# AD8232.net
KiCad netlist of a schematic drawn in EasyEDA
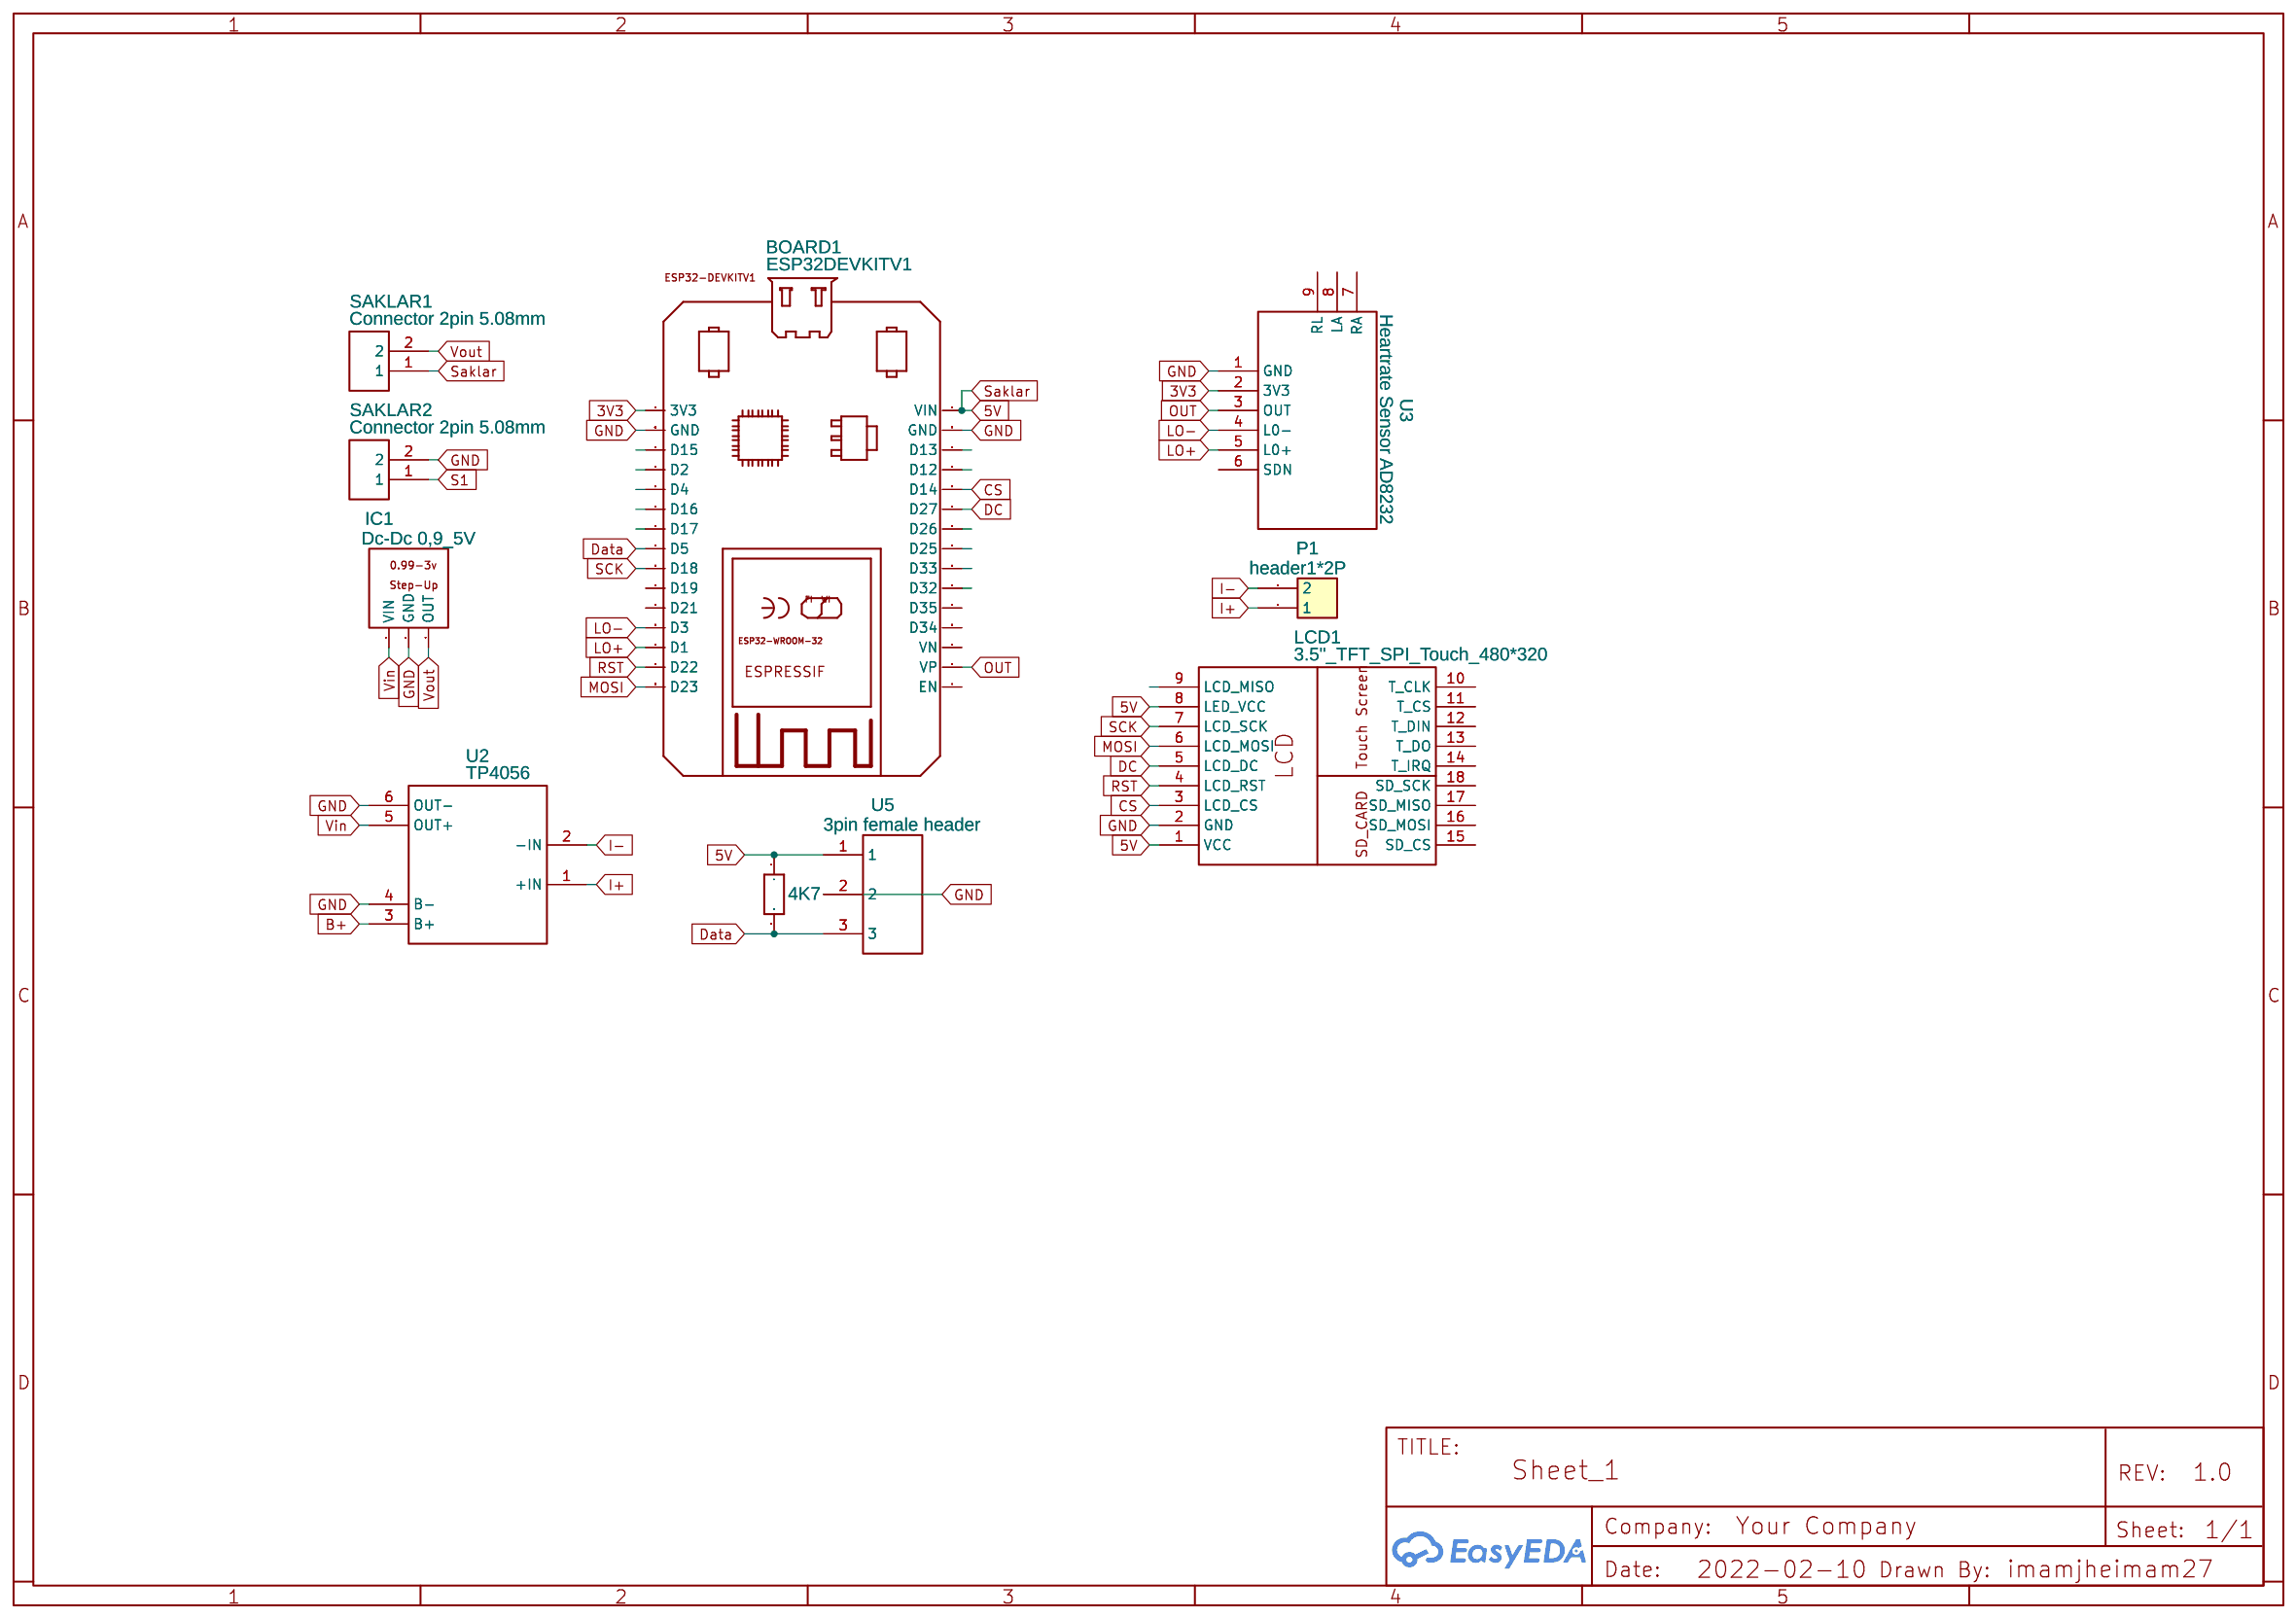
[diagram p0: schematic sheet]

(export (version "E")
  (design (tool "Eeschema 10.0.6"))
  (components
    (comp (ref "4K7") (value ".") (libsource (lib "") (part "NFR25H0002208J")))
    (comp (ref "BOARD1") (value "ESP32DEVKITV1") (libsource (lib "") (part "ESP32DEVKITV1")))
    (comp (ref "IC1") (value "Dc-Dc 0,9_5V") (libsource (lib "") (part "Dc-Dc 0,9_5V")))
    (comp (ref "LCD1")
      (value "3.5\"_TFT_SPI_Touch_480*320")
      (fields (field (name "BOM_Manufacturer Part") "ILI 9488"))
      (libsource (lib "") (part "3.5&quot;_TFT_SPI_Touch_480*320"))
    )
    (comp (ref "P1") (value "header1*2P") (libsource (lib "") (part "header1*2P")))
    (comp (ref "SAKLAR1") (value "Connector 2pin 5.08mm") (libsource (lib "") (part "Connector 2pin 5.08mm")))
    (comp (ref "SAKLAR2") (value "Connector 2pin 5.08mm") (libsource (lib "") (part "Connector 2pin 5.08mm")))
    (comp (ref "U2") (value "TP4056") (libsource (lib "") (part "TP4056")))
    (comp (ref "U3") (value "Heartrate Sensor AD8232") (libsource (lib "") (part "Heartrate Sensor AD8232")))
    (comp (ref "U5") (value "3pin female header") (libsource (lib "") (part "3pin female header")))
  )
  (nets
    (net (code "1") (name "3V3") (class "Default")
      (node (ref "BOARD1") (pin "3V3") (pinfunction "3V3_3V3") (pintype "bidirectional"))
      (node (ref "U3") (pin "2") (pinfunction "3V3_2") (pintype "unspecified"))
    )
    (net (code "2") (name "5V") (class "Default")
      (node (ref "4K7") (pin "1") (pinfunction "1_1") (pintype "bidirectional"))
      (node (ref "BOARD1") (pin "VIN") (pinfunction "VIN_VIN") (pintype "bidirectional"))
      (node (ref "LCD1") (pin "1") (pinfunction "VCC_1") (pintype "unspecified"))
      (node (ref "LCD1") (pin "8") (pinfunction "LED_VCC_8") (pintype "unspecified"))
      (node (ref "SAKLAR1") (pin "1") (pinfunction "1_1") (pintype "unspecified"))
      (node (ref "U5") (pin "1") (pinfunction "1_1") (pintype "unspecified"))
    )
    (net (code "3") (name "B+") (class "Default")
      (node (ref "U2") (pin "3") (pinfunction "B+_3") (pintype "unspecified"))
    )
    (net (code "4") (name "CS") (class "Default")
      (node (ref "BOARD1") (pin "D14") (pinfunction "D14_D14") (pintype "bidirectional"))
      (node (ref "LCD1") (pin "3") (pinfunction "LCD_CS_3") (pintype "unspecified"))
    )
    (net (code "5") (name "DC") (class "Default")
      (node (ref "BOARD1") (pin "D27") (pinfunction "D27_D27") (pintype "bidirectional"))
      (node (ref "LCD1") (pin "5") (pinfunction "LCD_DC_5") (pintype "unspecified"))
    )
    (net (code "6") (name "Data") (class "Default")
      (node (ref "4K7") (pin "2") (pinfunction "2_2") (pintype "bidirectional"))
      (node (ref "BOARD1") (pin "D5") (pinfunction "D5_D5") (pintype "bidirectional"))
      (node (ref "U5") (pin "3") (pinfunction "3_3") (pintype "unspecified"))
    )
    (net (code "7") (name "GND") (class "Default")
      (node (ref "BOARD1") (pin "GND") (pinfunction "GND_GND") (pintype "bidirectional"))
      (node (ref "BOARD1") (pin "GND@1") (pinfunction "GND_GND@1") (pintype "bidirectional"))
      (node (ref "IC1") (pin "2") (pinfunction "GND_2") (pintype "unspecified"))
      (node (ref "LCD1") (pin "2") (pinfunction "GND_2") (pintype "unspecified"))
      (node (ref "SAKLAR2") (pin "2") (pinfunction "2_2") (pintype "unspecified"))
      (node (ref "U2") (pin "4") (pinfunction "B-_4") (pintype "unspecified"))
      (node (ref "U2") (pin "6") (pinfunction "OUT-_6") (pintype "unspecified"))
      (node (ref "U3") (pin "1") (pinfunction "GND_1") (pintype "unspecified"))
      (node (ref "U5") (pin "2") (pinfunction "2_2") (pintype "unspecified"))
    )
    (net (code "8") (name "I+") (class "Default")
      (node (ref "P1") (pin "1") (pinfunction "1_1") (pintype "input"))
      (node (ref "U2") (pin "1") (pinfunction "+IN_1") (pintype "unspecified"))
    )
    (net (code "9") (name "I-") (class "Default")
      (node (ref "P1") (pin "2") (pinfunction "2_2") (pintype "input"))
      (node (ref "U2") (pin "2") (pinfunction "-IN_2") (pintype "unspecified"))
    )
    (net (code "10") (name "LO+") (class "Default")
      (node (ref "BOARD1") (pin "D1") (pinfunction "D1_D1") (pintype "bidirectional"))
      (node (ref "U3") (pin "5") (pinfunction "L0+_5") (pintype "unspecified"))
    )
    (net (code "11") (name "LO-") (class "Default")
      (node (ref "BOARD1") (pin "D3") (pinfunction "D3_D3") (pintype "bidirectional"))
      (node (ref "U3") (pin "4") (pinfunction "L0-_4") (pintype "unspecified"))
    )
    (net (code "12") (name "MOSI") (class "Default")
      (node (ref "BOARD1") (pin "D23") (pinfunction "D23_D23") (pintype "bidirectional"))
      (node (ref "LCD1") (pin "6") (pinfunction "LCD_MOSI_6") (pintype "unspecified"))
    )
    (net (code "13") (name "OUT") (class "Default")
      (node (ref "BOARD1") (pin "VP") (pinfunction "VP_VP") (pintype "bidirectional"))
      (node (ref "U3") (pin "3") (pinfunction "OUT_3") (pintype "unspecified"))
    )
    (net (code "14") (name "RST") (class "Default")
      (node (ref "BOARD1") (pin "D22") (pinfunction "D22_D22") (pintype "bidirectional"))
      (node (ref "LCD1") (pin "4") (pinfunction "LCD_RST_4") (pintype "unspecified"))
    )
    (net (code "15") (name "S1") (class "Default")
      (node (ref "SAKLAR2") (pin "1") (pinfunction "1_1") (pintype "unspecified"))
    )
    (net (code "16") (name "SCK") (class "Default")
      (node (ref "BOARD1") (pin "D18") (pinfunction "D18_D18") (pintype "bidirectional"))
      (node (ref "LCD1") (pin "7") (pinfunction "LCD_SCK_7") (pintype "unspecified"))
    )
    (net (code "17") (name "Vin") (class "Default")
      (node (ref "IC1") (pin "1") (pinfunction "VIN_1") (pintype "unspecified"))
      (node (ref "U2") (pin "5") (pinfunction "OUT+_5") (pintype "unspecified"))
    )
    (net (code "18") (name "Vout") (class "Default")
      (node (ref "IC1") (pin "3") (pinfunction "OUT_3") (pintype "unspecified"))
      (node (ref "SAKLAR1") (pin "2") (pinfunction "2_2") (pintype "unspecified"))
    )
    (net (code "19") (name "unconnected-(BOARD1-PadD2)") (class "Default")
      (node (ref "BOARD1") (pin "D2") (pinfunction "D2_D2") (pintype "bidirectional"))
    )
    (net (code "20") (name "unconnected-(BOARD1-PadD4)") (class "Default")
      (node (ref "BOARD1") (pin "D4") (pinfunction "D4_D4") (pintype "bidirectional"))
    )
    (net (code "21") (name "unconnected-(BOARD1-PadD12)") (class "Default")
      (node (ref "BOARD1") (pin "D12") (pinfunction "D12_D12") (pintype "bidirectional"))
    )
    (net (code "22") (name "unconnected-(BOARD1-PadD13)") (class "Default")
      (node (ref "BOARD1") (pin "D13") (pinfunction "D13_D13") (pintype "bidirectional"))
    )
    (net (code "23") (name "unconnected-(BOARD1-PadD15)") (class "Default")
      (node (ref "BOARD1") (pin "D15") (pinfunction "D15_D15") (pintype "bidirectional"))
    )
    (net (code "24") (name "unconnected-(BOARD1-PadD16)") (class "Default")
      (node (ref "BOARD1") (pin "D16") (pinfunction "D16_D16") (pintype "bidirectional"))
    )
    (net (code "25") (name "unconnected-(BOARD1-PadD17)") (class "Default")
      (node (ref "BOARD1") (pin "D17") (pinfunction "D17_D17") (pintype "bidirectional"))
    )
    (net (code "26") (name "unconnected-(BOARD1-PadD19)") (class "Default")
      (node (ref "BOARD1") (pin "D19") (pinfunction "D19_D19") (pintype "bidirectional"))
    )
    (net (code "27") (name "unconnected-(BOARD1-PadD21)") (class "Default")
      (node (ref "BOARD1") (pin "D21") (pinfunction "D21_D21") (pintype "bidirectional"))
    )
    (net (code "28") (name "unconnected-(BOARD1-PadD25)") (class "Default")
      (node (ref "BOARD1") (pin "D25") (pinfunction "D25_D25") (pintype "bidirectional"))
    )
    (net (code "29") (name "unconnected-(BOARD1-PadD26)") (class "Default")
      (node (ref "BOARD1") (pin "D26") (pinfunction "D26_D26") (pintype "bidirectional"))
    )
    (net (code "30") (name "unconnected-(BOARD1-PadD32)") (class "Default")
      (node (ref "BOARD1") (pin "D32") (pinfunction "D32_D32") (pintype "bidirectional"))
    )
    (net (code "31") (name "unconnected-(BOARD1-PadD33)") (class "Default")
      (node (ref "BOARD1") (pin "D33") (pinfunction "D33_D33") (pintype "bidirectional"))
    )
    (net (code "32") (name "unconnected-(BOARD1-PadD34)") (class "Default")
      (node (ref "BOARD1") (pin "D34") (pinfunction "D34_D34") (pintype "bidirectional"))
    )
    (net (code "33") (name "unconnected-(BOARD1-PadD35)") (class "Default")
      (node (ref "BOARD1") (pin "D35") (pinfunction "D35_D35") (pintype "bidirectional"))
    )
    (net (code "34") (name "unconnected-(BOARD1-PadEN)") (class "Default")
      (node (ref "BOARD1") (pin "EN") (pinfunction "EN_EN") (pintype "bidirectional"))
    )
    (net (code "35") (name "unconnected-(BOARD1-PadVN)") (class "Default")
      (node (ref "BOARD1") (pin "VN") (pinfunction "VN_VN") (pintype "bidirectional"))
    )
    (net (code "36") (name "unconnected-(LCD1-LCD_MISO-Pad9)") (class "Default")
      (node (ref "LCD1") (pin "9") (pinfunction "LCD_MISO_9") (pintype "unspecified"))
    )
    (net (code "37") (name "unconnected-(LCD1-SD_CS-Pad15)") (class "Default")
      (node (ref "LCD1") (pin "15") (pinfunction "SD_CS_15") (pintype "unspecified"))
    )
    (net (code "38") (name "unconnected-(LCD1-SD_MISO-Pad17)") (class "Default")
      (node (ref "LCD1") (pin "17") (pinfunction "SD_MISO_17") (pintype "unspecified"))
    )
    (net (code "39") (name "unconnected-(LCD1-SD_MOSI-Pad16)") (class "Default")
      (node (ref "LCD1") (pin "16") (pinfunction "SD_MOSI_16") (pintype "unspecified"))
    )
    (net (code "40") (name "unconnected-(LCD1-SD_SCK-Pad18)") (class "Default")
      (node (ref "LCD1") (pin "18") (pinfunction "SD_SCK_18") (pintype "unspecified"))
    )
    (net (code "41") (name "unconnected-(LCD1-T_CLK-Pad10)") (class "Default")
      (node (ref "LCD1") (pin "10") (pinfunction "T_CLK_10") (pintype "unspecified"))
    )
    (net (code "42") (name "unconnected-(LCD1-T_CS-Pad11)") (class "Default")
      (node (ref "LCD1") (pin "11") (pinfunction "T_CS_11") (pintype "unspecified"))
    )
    (net (code "43") (name "unconnected-(LCD1-T_DIN-Pad12)") (class "Default")
      (node (ref "LCD1") (pin "12") (pinfunction "T_DIN_12") (pintype "unspecified"))
    )
    (net (code "44") (name "unconnected-(LCD1-T_DO-Pad13)") (class "Default")
      (node (ref "LCD1") (pin "13") (pinfunction "T_DO_13") (pintype "unspecified"))
    )
    (net (code "45") (name "unconnected-(LCD1-T_IRQ-Pad14)") (class "Default")
      (node (ref "LCD1") (pin "14") (pinfunction "T_IRQ_14") (pintype "unspecified"))
    )
    (net (code "46") (name "unconnected-(U3-LA-Pad8)") (class "Default")
      (node (ref "U3") (pin "8") (pinfunction "LA_8") (pintype "unspecified"))
    )
    (net (code "47") (name "unconnected-(U3-RA-Pad7)") (class "Default")
      (node (ref "U3") (pin "7") (pinfunction "RA_7") (pintype "unspecified"))
    )
    (net (code "48") (name "unconnected-(U3-RL-Pad9)") (class "Default")
      (node (ref "U3") (pin "9") (pinfunction "RL_9") (pintype "unspecified"))
    )
    (net (code "49") (name "unconnected-(U3-SDN-Pad6)") (class "Default")
      (node (ref "U3") (pin "6") (pinfunction "SDN_6") (pintype "unspecified"))
    )
  )
)
